# H1maria_v120_schematic.net
KiCad netlist of a schematic drawn in EAGLE
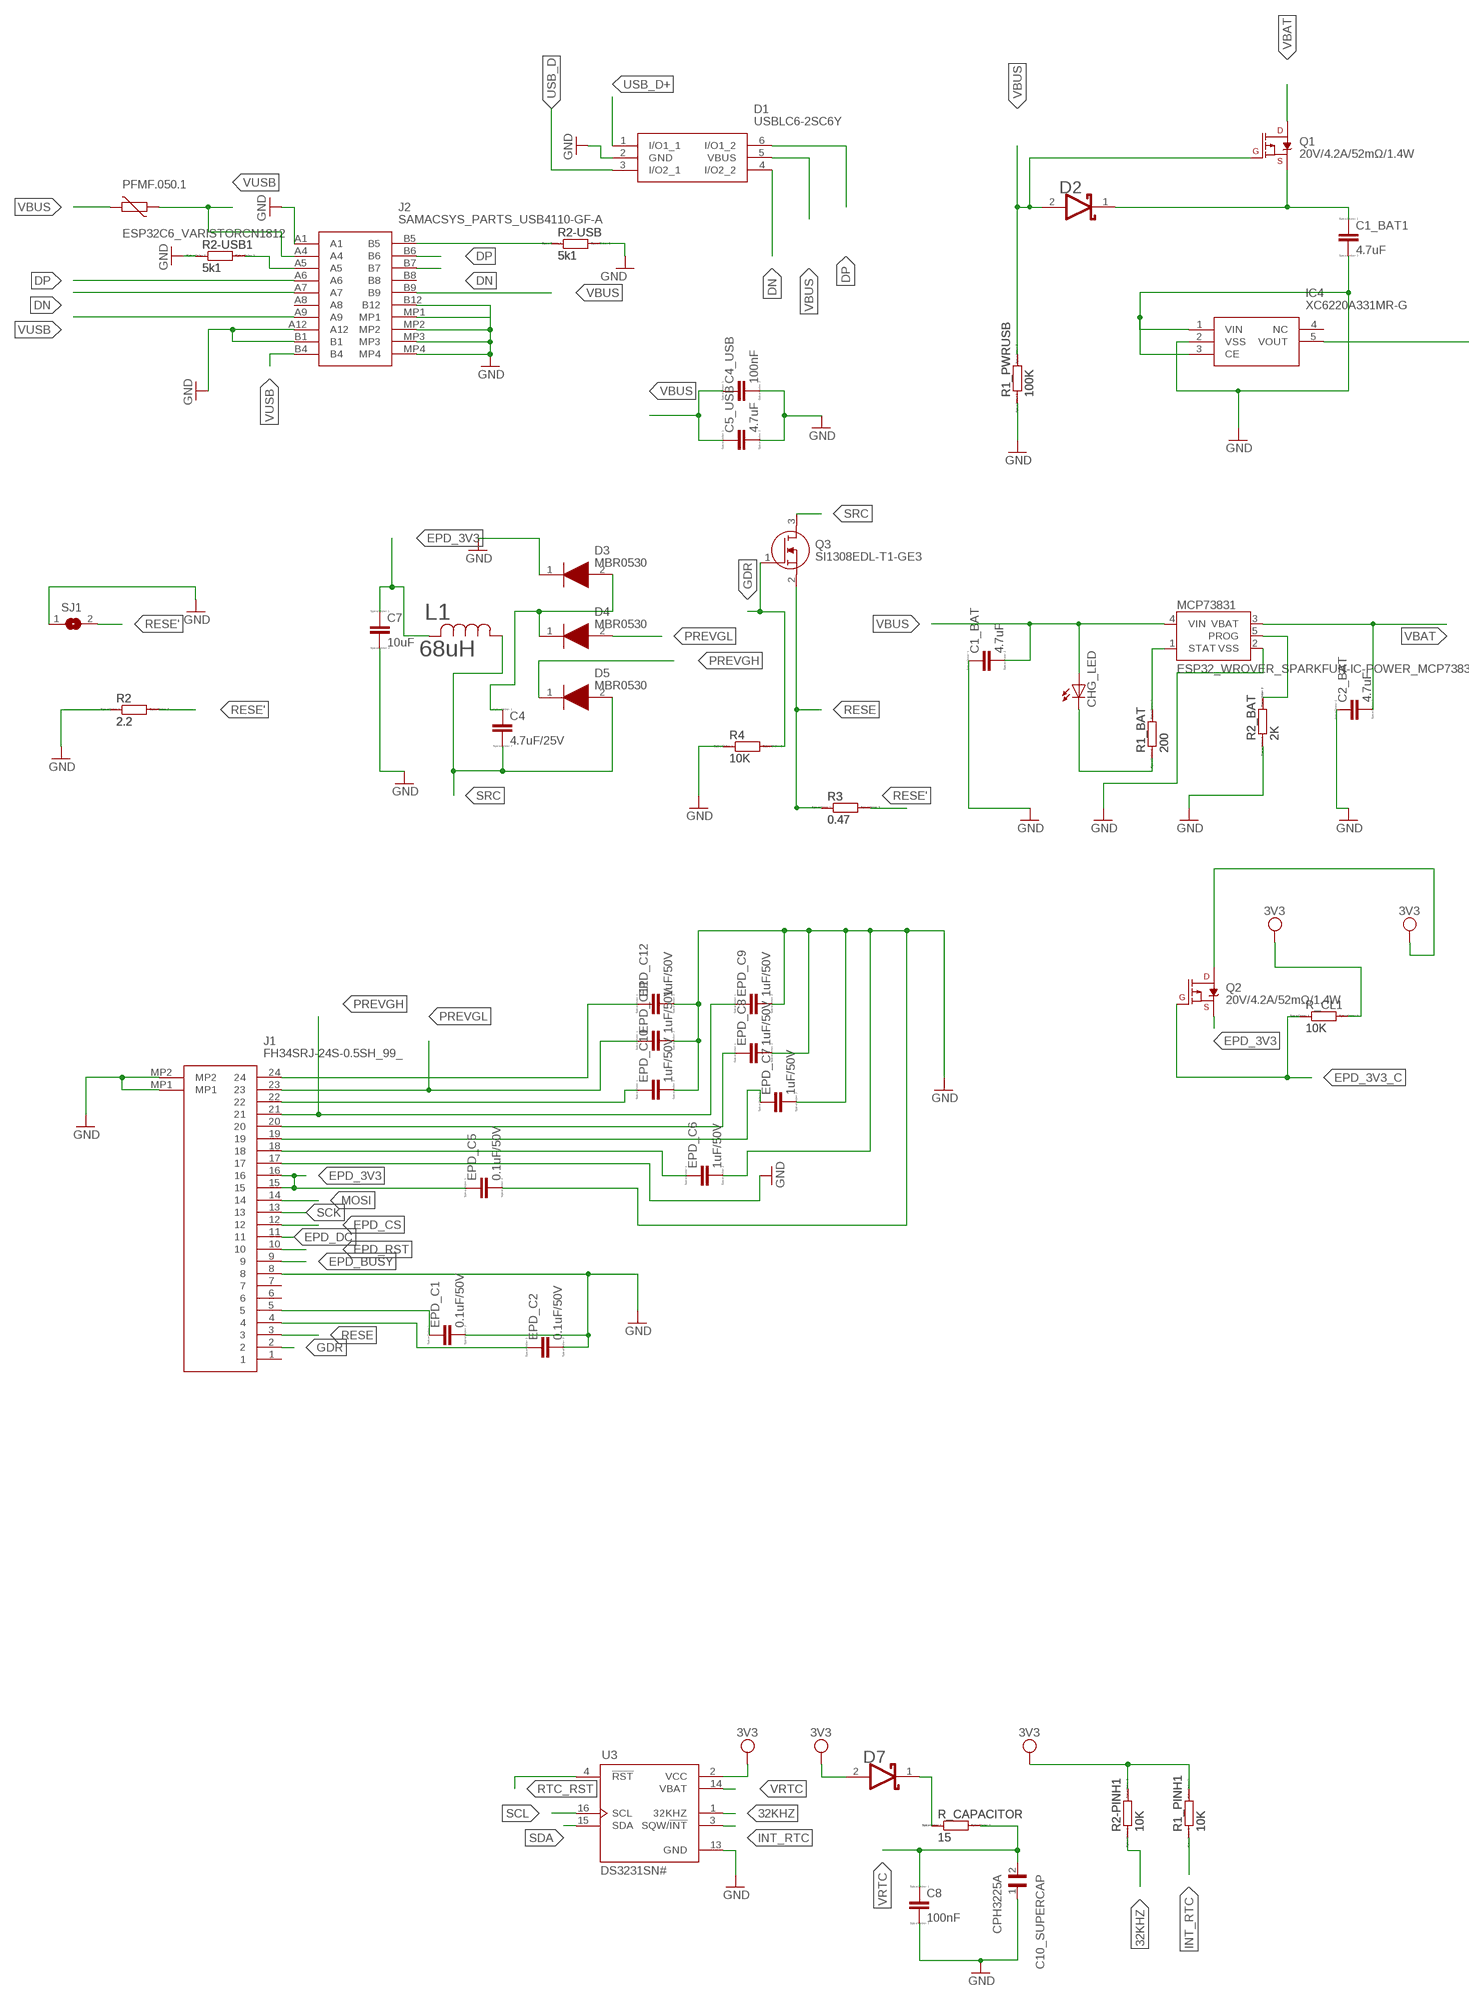
[diagram p0: schematic, sheet 1, part 1 of 2]
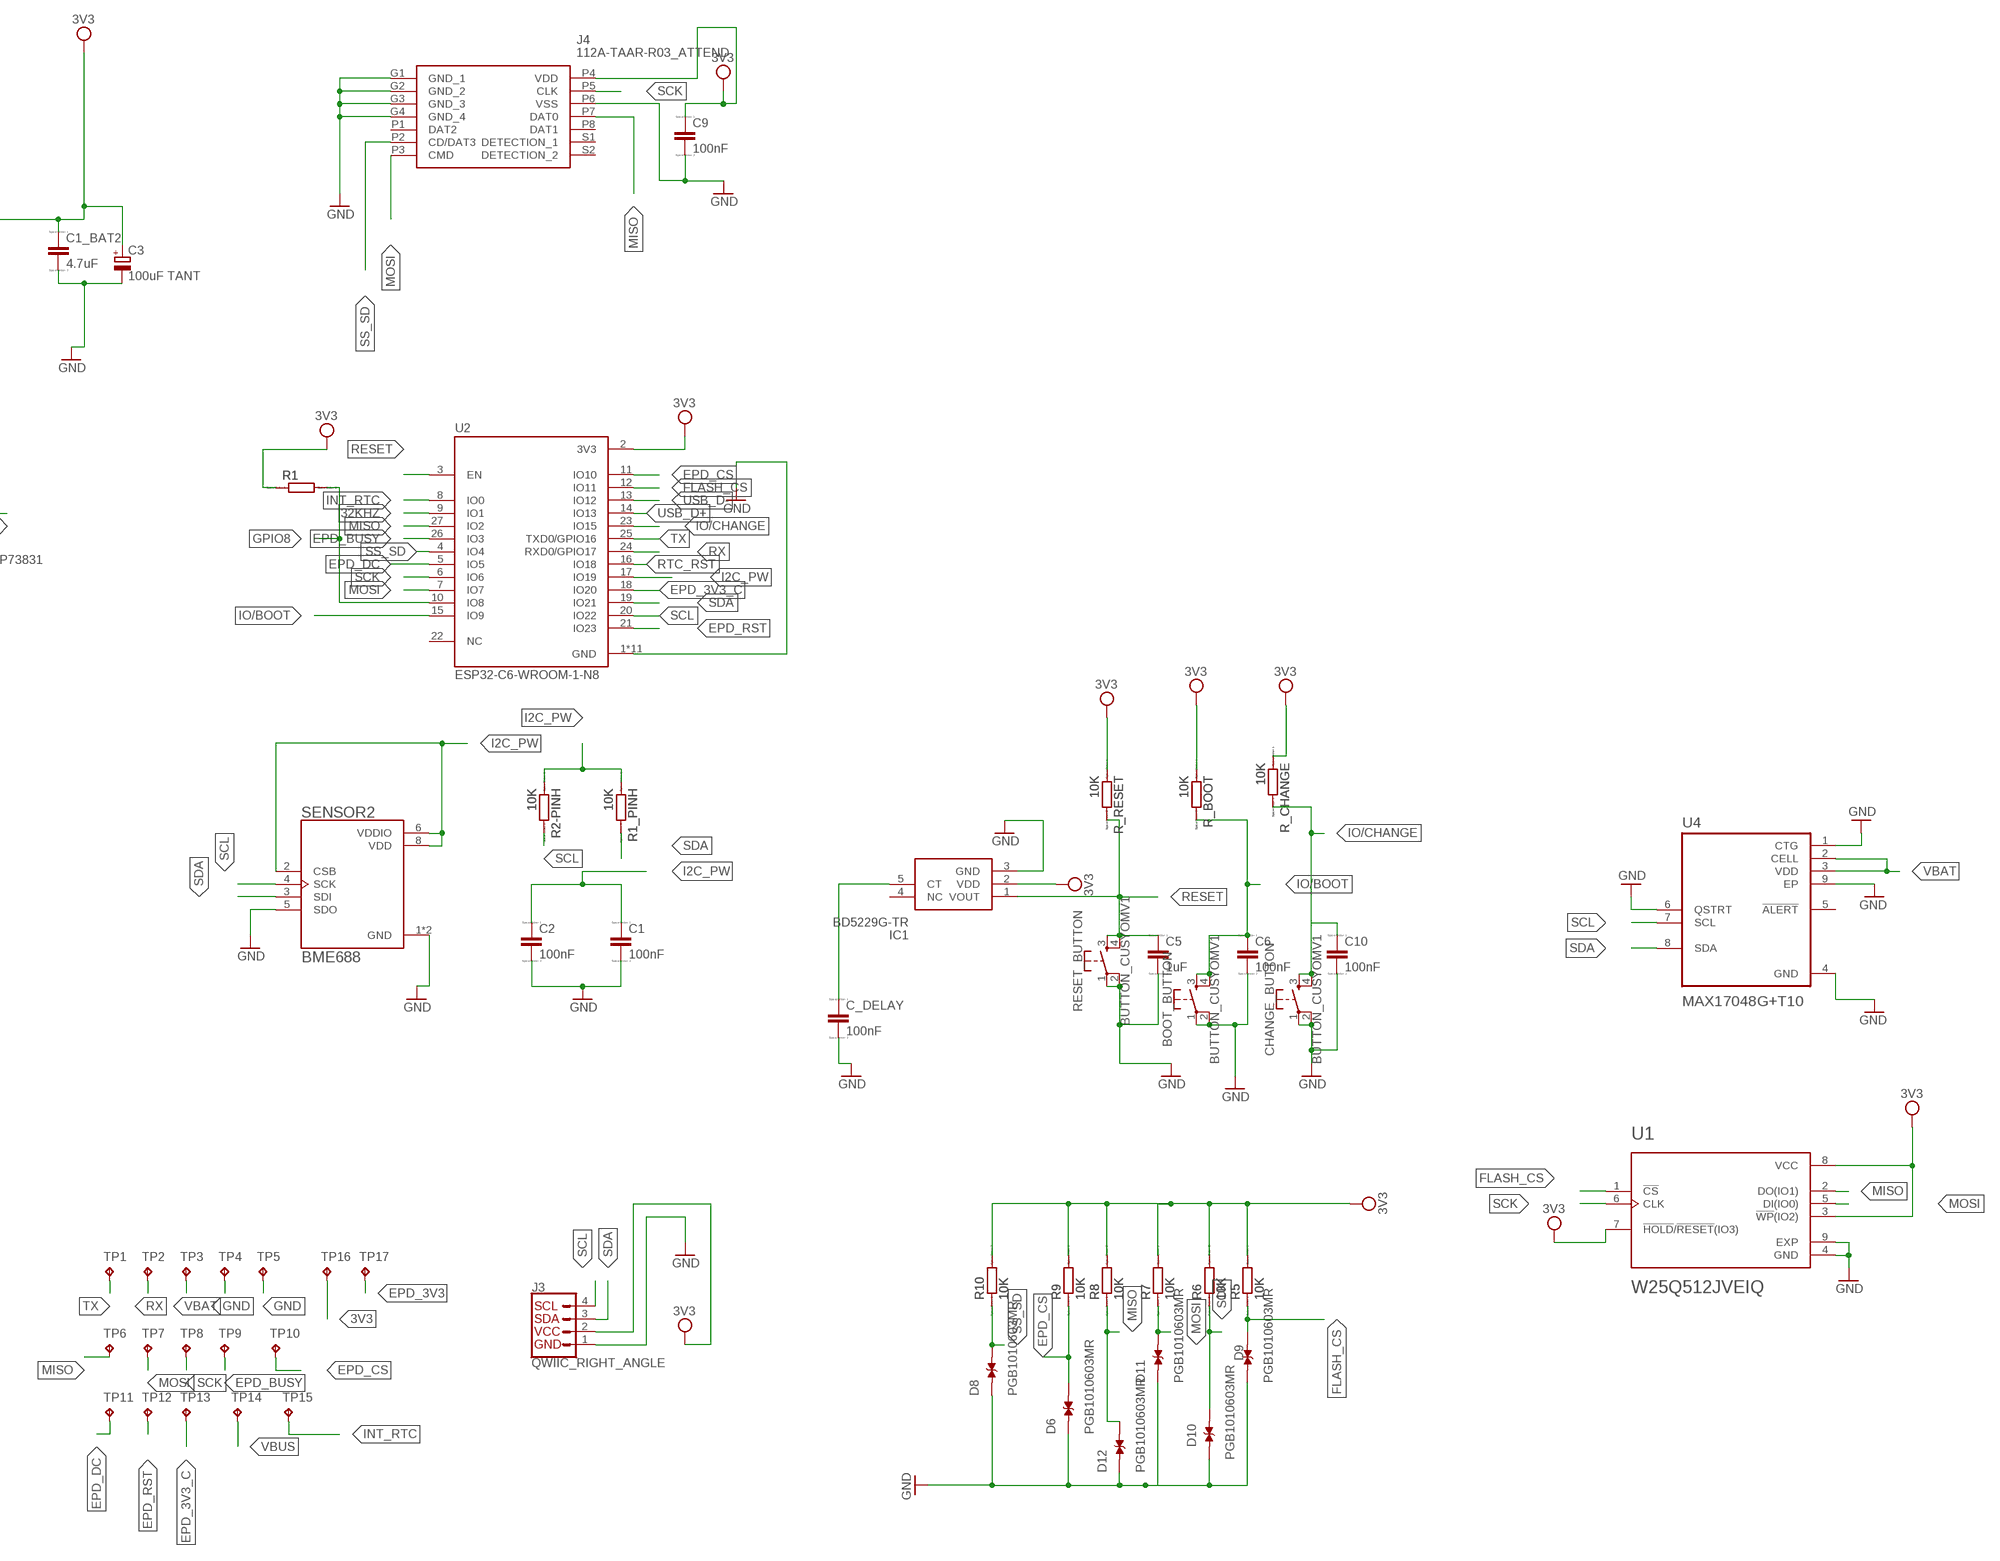
[diagram p1: schematic, sheet 1, part 2 of 2]

(export (version "E")
  (design (tool "Eeschema 10.0.6"))
  (components
    (comp (ref "BOOT_BUTTON")
      (value "BUTTON_CUSYOMV1")
      (footprint "eagle-import:MYBUTTON")
      (libsource (lib "eagle-import") (part "BUTTON_CUSYOMV1"))
    )
    (comp (ref "C1")
      (value "100nF")
      (footprint "eagle-import:ESP32_WROVER_EAGLE-LTSPICE_C0402")
      (libsource (lib "eagle-import") (part "ESP32_WROVER_EAGLE-LTSPICE_CC0402"))
    )
    (comp (ref "C1_BAT")
      (value "4.7uF")
      (footprint "eagle-import:EAGLE-LTSPICE_C0402")
      (libsource (lib "eagle-import") (part "EAGLE-LTSPICE_CC0402"))
    )
    (comp (ref "C1_BAT1")
      (value "4.7uF")
      (footprint "eagle-import:EAGLE-LTSPICE_C0402")
      (libsource (lib "eagle-import") (part "EAGLE-LTSPICE_CC0402"))
    )
    (comp (ref "C1_BAT2")
      (value "4.7uF")
      (footprint "eagle-import:EAGLE-LTSPICE_C0402")
      (libsource (lib "eagle-import") (part "EAGLE-LTSPICE_CC0402"))
    )
    (comp (ref "C2")
      (value "100nF")
      (footprint "eagle-import:ESP32_WROVER_EAGLE-LTSPICE_C0402")
      (libsource (lib "eagle-import") (part "ESP32_WROVER_EAGLE-LTSPICE_CC0402"))
    )
    (comp (ref "C2_BAT")
      (value "4.7uF")
      (footprint "eagle-import:EAGLE-LTSPICE_C0402")
      (libsource (lib "eagle-import") (part "EAGLE-LTSPICE_CC0402"))
    )
    (comp (ref "C3")
      (value "100uF TANT")
      (footprint "eagle-import:RCL_CT3528")
      (libsource (lib "eagle-import") (part "RCL_CPOL-EUCT3528"))
    )
    (comp (ref "C4")
      (value "4.7uF/25V")
      (footprint "eagle-import:ESP32_WROVER_EAGLE-LTSPICE_C0402")
      (libsource (lib "eagle-import") (part "ESP32_WROVER_EAGLE-LTSPICE_CC0402"))
    )
    (comp (ref "C4_USB")
      (value "100nF")
      (footprint "eagle-import:EAGLE-LTSPICE_C0402")
      (libsource (lib "eagle-import") (part "EAGLE-LTSPICE_CC0402"))
    )
    (comp (ref "C5")
      (value "1uF")
      (footprint "eagle-import:EAGLE-LTSPICE_C0402")
      (libsource (lib "eagle-import") (part "EAGLE-LTSPICE_CC0402"))
    )
    (comp (ref "C5_USB")
      (value "4.7uF")
      (footprint "eagle-import:EAGLE-LTSPICE_C0402")
      (libsource (lib "eagle-import") (part "EAGLE-LTSPICE_CC0402"))
    )
    (comp (ref "C6")
      (value "100nF")
      (footprint "eagle-import:EAGLE-LTSPICE_C0402")
      (libsource (lib "eagle-import") (part "EAGLE-LTSPICE_CC0402"))
    )
    (comp (ref "C7")
      (value "10uF")
      (footprint "eagle-import:ESP32_WROVER_EAGLE-LTSPICE_C0402")
      (libsource (lib "eagle-import") (part "ESP32_WROVER_EAGLE-LTSPICE_CC0402"))
    )
    (comp (ref "C8")
      (value "100nF")
      (footprint "eagle-import:EAGLE-LTSPICE_C0402")
      (libsource (lib "eagle-import") (part "EAGLE-LTSPICE_CC0402"))
    )
    (comp (ref "C9")
      (value "100nF")
      (footprint "eagle-import:ESP32_WROVER_EAGLE-LTSPICE_C0402")
      (libsource (lib "eagle-import") (part "ESP32_WROVER_EAGLE-LTSPICE_CC0402"))
    )
    (comp (ref "C10")
      (value "100nF")
      (footprint "eagle-import:EAGLE-LTSPICE_C0402")
      (libsource (lib "eagle-import") (part "EAGLE-LTSPICE_CC0402"))
    )
    (comp (ref "C10_SUPERCAP")
      (value "CPH3225A")
      (footprint "eagle-import:CAPCP3225X100N")
      (fields (field (name "MF") "Seiko Instruments"))
      (libsource (lib "eagle-import") (part "CPH3225A"))
    )
    (comp (ref "CHANGE_BUTTON")
      (value "BUTTON_CUSYOMV1")
      (footprint "eagle-import:MYBUTTON")
      (libsource (lib "eagle-import") (part "BUTTON_CUSYOMV1"))
    )
    (comp (ref "CHG_LED")
      (value "ADAFRUIT_LEDCHIP-LED0603")
      (footprint "eagle-import:ADAFRUIT_CHIP-LED0603")
      (libsource (lib "eagle-import") (part "ADAFRUIT_LEDCHIP-LED0603"))
    )
    (comp (ref "C_DELAY")
      (value "100nF")
      (footprint "eagle-import:EAGLE-LTSPICE_C0402")
      (libsource (lib "eagle-import") (part "EAGLE-LTSPICE_CC0402"))
    )
    (comp (ref "D1")
      (value "USBLC6-2SC6Y")
      (footprint "eagle-import:SOT95P280X145-6N")
      (fields (field (name "MF") "STMicroelectronics"))
      (libsource (lib "eagle-import") (part "USBLC6-2SC6Y"))
    )
    (comp (ref "D2")
      (value "SD0805S020S1R0")
      (footprint "eagle-import:ESP32_WROVER_AVX---SD0805S020S1R0_AVX_SD0805S020S1R0_0")
      (fields
        (field (name "DIGIKEY_PART_NUMBER") "478-7800-1-ND")
        (field (name "MF") "AVX")
        (field (name "MOUSER_PART_NUMBER") "581-SD0805S020S1R0")
      )
      (libsource (lib "eagle-import") (part "ESP32_WROVER_AVX---SD0805S020S1R0_AVX_SD0805S020S1R0_0_0AVX_SD0805S020S1R0_0_0"))
    )
    (comp (ref "D3")
      (value "MBR0530")
      (footprint "eagle-import:SOD3716X135N")
      (fields (field (name "MF") "ON Semiconductor"))
      (libsource (lib "eagle-import") (part "MBR0530"))
    )
    (comp (ref "D4")
      (value "MBR0530")
      (footprint "eagle-import:SOD3716X135N")
      (fields (field (name "MF") "ON Semiconductor"))
      (libsource (lib "eagle-import") (part "MBR0530"))
    )
    (comp (ref "D5")
      (value "MBR0530")
      (footprint "eagle-import:SOD3716X135N")
      (fields (field (name "MF") "ON Semiconductor"))
      (libsource (lib "eagle-import") (part "MBR0530"))
    )
    (comp (ref "D6")
      (value "PGB1010603MR")
      (footprint "eagle-import:DIOC1608X36N")
      (fields (field (name "MF") "Littelfuse Inc."))
      (libsource (lib "eagle-import") (part "PGB1010603MR"))
    )
    (comp (ref "D7")
      (value "ESP32_WROVER_AVX---SD0805S020S1R0_AVX_SD0805S020S1R0_0_0AVX_SD0805S020S1R0_0_0")
      (footprint "eagle-import:ESP32_WROVER_AVX---SD0805S020S1R0_AVX_SD0805S020S1R0_0")
      (fields
        (field (name "DIGIKEY_PART_NUMBER") "478-7800-1-ND")
        (field (name "MF") "AVX")
        (field (name "MOUSER_PART_NUMBER") "581-SD0805S020S1R0")
      )
      (libsource (lib "eagle-import") (part "ESP32_WROVER_AVX---SD0805S020S1R0_AVX_SD0805S020S1R0_0_0AVX_SD0805S020S1R0_0_0"))
    )
    (comp (ref "D8")
      (value "PGB1010603MR")
      (footprint "eagle-import:DIOC1608X36N")
      (fields (field (name "MF") "Littelfuse Inc."))
      (libsource (lib "eagle-import") (part "PGB1010603MR"))
    )
    (comp (ref "D9")
      (value "PGB1010603MR")
      (footprint "eagle-import:DIOC1608X36N")
      (fields (field (name "MF") "Littelfuse Inc."))
      (libsource (lib "eagle-import") (part "PGB1010603MR"))
    )
    (comp (ref "D10")
      (value "PGB1010603MR")
      (footprint "eagle-import:DIOC1608X36N")
      (fields (field (name "MF") "Littelfuse Inc."))
      (libsource (lib "eagle-import") (part "PGB1010603MR"))
    )
    (comp (ref "D11")
      (value "PGB1010603MR")
      (footprint "eagle-import:DIOC1608X36N")
      (fields (field (name "MF") "Littelfuse Inc."))
      (libsource (lib "eagle-import") (part "PGB1010603MR"))
    )
    (comp (ref "D12")
      (value "PGB1010603MR")
      (footprint "eagle-import:DIOC1608X36N")
      (fields (field (name "MF") "Littelfuse Inc."))
      (libsource (lib "eagle-import") (part "PGB1010603MR"))
    )
    (comp (ref "EPD_C1")
      (value "0.1uF/50V")
      (footprint "eagle-import:EAGLE-LTSPICE_C0402")
      (libsource (lib "eagle-import") (part "EAGLE-LTSPICE_CC0402"))
    )
    (comp (ref "EPD_C2")
      (value "0.1uF/50V")
      (footprint "eagle-import:EAGLE-LTSPICE_C0402")
      (libsource (lib "eagle-import") (part "EAGLE-LTSPICE_CC0402"))
    )
    (comp (ref "EPD_C5")
      (value "0.1uF/50V")
      (footprint "eagle-import:EAGLE-LTSPICE_C0402")
      (libsource (lib "eagle-import") (part "EAGLE-LTSPICE_CC0402"))
    )
    (comp (ref "EPD_C6")
      (value "1uF/50V")
      (footprint "eagle-import:EAGLE-LTSPICE_C0402")
      (libsource (lib "eagle-import") (part "EAGLE-LTSPICE_CC0402"))
    )
    (comp (ref "EPD_C7")
      (value "1uF/50V")
      (footprint "eagle-import:EAGLE-LTSPICE_C0402")
      (libsource (lib "eagle-import") (part "EAGLE-LTSPICE_CC0402"))
    )
    (comp (ref "EPD_C8")
      (value "1uF/50V")
      (footprint "eagle-import:EAGLE-LTSPICE_C0402")
      (libsource (lib "eagle-import") (part "EAGLE-LTSPICE_CC0402"))
    )
    (comp (ref "EPD_C9")
      (value "1uF/50V")
      (footprint "eagle-import:EAGLE-LTSPICE_C0402")
      (libsource (lib "eagle-import") (part "EAGLE-LTSPICE_CC0402"))
    )
    (comp (ref "EPD_C10")
      (value "1uF/50V")
      (footprint "eagle-import:EAGLE-LTSPICE_C0402")
      (libsource (lib "eagle-import") (part "EAGLE-LTSPICE_CC0402"))
    )
    (comp (ref "EPD_C11")
      (value "1uF/50V")
      (footprint "eagle-import:EAGLE-LTSPICE_C0402")
      (libsource (lib "eagle-import") (part "EAGLE-LTSPICE_CC0402"))
    )
    (comp (ref "EPD_C12")
      (value "1uF/50V")
      (footprint "eagle-import:EAGLE-LTSPICE_C0402")
      (libsource (lib "eagle-import") (part "EAGLE-LTSPICE_CC0402"))
    )
    (comp (ref "IC1")
      (value "BD5229G-TR")
      (footprint "eagle-import:SOT95P280X125-5N")
      (fields (field (name "MOUSER_PART_NUMBER") "755-BD5229G-TR"))
      (libsource (lib "eagle-import") (part "BD5229G-TR"))
    )
    (comp (ref "IC4")
      (value "XC6220A331MR-G")
      (footprint "eagle-import:SOT95P280X120-5N")
      (fields (field (name "MOUSER_PART_NUMBER") "865-XC6220A331MR-G"))
      (libsource (lib "eagle-import") (part "XC6220A331MR-G"))
    )
    (comp (ref "J1")
      (value "FH34SRJ-24S-0.5SH_99_")
      (footprint "eagle-import:FH34SRJ24S05SH99")
      (fields
        (field (name "MANUFACTURER_PART_NUMBER") "FH34SRJ-24S-0.5SH(99)")
        (field (name "MOUSER_PART_NUMBER") "798-FH34SRJ24S05SH99")
      )
      (libsource (lib "eagle-import") (part "FH34SRJ-24S-0.5SH_99_"))
    )
    (comp (ref "J2")
      (value "SAMACSYS_PARTS_USB4110-GF-A")
      (footprint "eagle-import:SAMACSYS_PARTS_USB4110GFA")
      (fields
        (field (name "MANUFACTURER_PART_NUMBER") "USB4110-GF-A")
        (field (name "MOUSER_PART_NUMBER") "640-USB4110-GF-A")
      )
      (libsource (lib "eagle-import") (part "SAMACSYS_PARTS_USB4110-GF-A"))
    )
    (comp (ref "J3")
      (value "QWIIC_RIGHT_ANGLE")
      (footprint "eagle-import:JST04_1MM_RA")
      (libsource (lib "eagle-import") (part "QWIIC_CONNECTORJS-1MM"))
    )
    (comp (ref "J4")
      (value "112A-TAAR-R03_ATTEND")
      (footprint "eagle-import:112ATAARR03ATTEND")
      (fields (field (name "MANUFACTURER_PART_NUMBER") "112A-TAAR-R03 ATTEND"))
      (libsource (lib "eagle-import") (part "112A-TAAR-R03_ATTEND"))
    )
    (comp (ref "L1")
      (value "68uH")
      (footprint "eagle-import:IND_4828-WE-TPC_WRE")
      (fields
        (field (name "MANUFACTURER_PART_NUMBER") "744043680")
        (field (name "COPYRIGHT") "Copyright (C) 2024 Ultra Librarian. All rights reserved.")
      )
      (libsource (lib "eagle-import") (part "744043680IND_4828-WE-TPC_WRE"))
    )
    (comp (ref "MCP73831")
      (value "ESP32_WROVER_SPARKFUN-IC-POWER_MCP73831")
      (footprint "eagle-import:ESP32_WROVER_SPARKFUN-IC-POWER_SOT23-5")
      (libsource (lib "eagle-import") (part "ESP32_WROVER_SPARKFUN-IC-POWER_MCP73831"))
    )
    (comp (ref "PFMF.050.1")
      (value "ESP32C6_VARISTORCN1812")
      (footprint "eagle-import:ESP32C6_VARISTOR_CT_CN1812")
      (libsource (lib "eagle-import") (part "ESP32C6_VARISTORCN1812"))
    )
    (comp (ref "Q1")
      (value "20V/4.2A/52mΩ/1.4W")
      (footprint "eagle-import:ESP32_WROVER_SPARKFUN-DISCRETESEMI_SOT23-3")
      (libsource (lib "eagle-import") (part "ESP32_WROVER_SPARKFUN-DISCRETESEMI_MOSFET_PCH-DMG2305UX-7"))
    )
    (comp (ref "Q2")
      (value "20V/4.2A/52mΩ/1.4W")
      (footprint "eagle-import:ESP32_WROVER_SPARKFUN-DISCRETESEMI_SOT23-3")
      (libsource (lib "eagle-import") (part "ESP32_WROVER_SPARKFUN-DISCRETESEMI_MOSFET_PCH-DMG2305UX-7"))
    )
    (comp (ref "Q3")
      (value "SI1308EDL-T1-GE3")
      (footprint "eagle-import:SOT65P210X110-3N")
      (fields (field (name "MF") "Vishay Siliconix"))
      (libsource (lib "eagle-import") (part "SI1308EDL-T1-GE3"))
    )
    (comp (ref "R1")
      (value "ESP32_WROVER_EAGLE-LTSPICE_RR0402")
      (footprint "eagle-import:ESP32_WROVER_EAGLE-LTSPICE_R0402")
      (libsource (lib "eagle-import") (part "ESP32_WROVER_EAGLE-LTSPICE_RR0402"))
    )
    (comp (ref "R1_BAT")
      (value "200")
      (footprint "eagle-import:ESP32_WROVER_EAGLE-LTSPICE_R0402")
      (libsource (lib "eagle-import") (part "ESP32_WROVER_EAGLE-LTSPICE_RR0402"))
    )
    (comp (ref "R1_PINH")
      (value "10K")
      (footprint "eagle-import:ESP32_WROVER_EAGLE-LTSPICE_R0402")
      (libsource (lib "eagle-import") (part "ESP32_WROVER_EAGLE-LTSPICE_RR0402"))
    )
    (comp (ref "R1_PINH1")
      (value "10K")
      (footprint "eagle-import:ESP32_WROVER_EAGLE-LTSPICE_R0402")
      (libsource (lib "eagle-import") (part "ESP32_WROVER_EAGLE-LTSPICE_RR0402"))
    )
    (comp (ref "R1_PWRUSB")
      (value "100K")
      (footprint "eagle-import:ESP32_WROVER_EAGLE-LTSPICE_R0402")
      (libsource (lib "eagle-import") (part "ESP32_WROVER_EAGLE-LTSPICE_RR0402"))
    )
    (comp (ref "R2")
      (value "2.2")
      (footprint "eagle-import:ESP32_WROVER_EAGLE-LTSPICE_R0402")
      (libsource (lib "eagle-import") (part "ESP32_WROVER_EAGLE-LTSPICE_RR0402"))
    )
    (comp (ref "R2-PINH")
      (value "10K")
      (footprint "eagle-import:ESP32_WROVER_EAGLE-LTSPICE_R0402")
      (libsource (lib "eagle-import") (part "ESP32_WROVER_EAGLE-LTSPICE_RR0402"))
    )
    (comp (ref "R2-PINH1")
      (value "10K")
      (footprint "eagle-import:ESP32_WROVER_EAGLE-LTSPICE_R0402")
      (libsource (lib "eagle-import") (part "ESP32_WROVER_EAGLE-LTSPICE_RR0402"))
    )
    (comp (ref "R2-USB")
      (value "5k1")
      (footprint "eagle-import:ESP32_WROVER_EAGLE-LTSPICE_R0402")
      (libsource (lib "eagle-import") (part "ESP32_WROVER_EAGLE-LTSPICE_RR0402"))
    )
    (comp (ref "R2-USB1")
      (value "5k1")
      (footprint "eagle-import:ESP32_WROVER_EAGLE-LTSPICE_R0402")
      (libsource (lib "eagle-import") (part "ESP32_WROVER_EAGLE-LTSPICE_RR0402"))
    )
    (comp (ref "R2_BAT")
      (value "2K")
      (footprint "eagle-import:ESP32_WROVER_EAGLE-LTSPICE_R0402")
      (libsource (lib "eagle-import") (part "ESP32_WROVER_EAGLE-LTSPICE_RR0402"))
    )
    (comp (ref "R3")
      (value "0.47")
      (footprint "eagle-import:ESP32_WROVER_EAGLE-LTSPICE_R0402")
      (libsource (lib "eagle-import") (part "ESP32_WROVER_EAGLE-LTSPICE_RR0402"))
    )
    (comp (ref "R4")
      (value "10K")
      (footprint "eagle-import:ESP32_WROVER_EAGLE-LTSPICE_R0402")
      (libsource (lib "eagle-import") (part "ESP32_WROVER_EAGLE-LTSPICE_RR0402"))
    )
    (comp (ref "R5")
      (value "10K")
      (footprint "eagle-import:ESP32_WROVER_EAGLE-LTSPICE_R0402")
      (libsource (lib "eagle-import") (part "ESP32_WROVER_EAGLE-LTSPICE_RR0402"))
    )
    (comp (ref "R6")
      (value "10K")
      (footprint "eagle-import:ESP32_WROVER_EAGLE-LTSPICE_R0402")
      (libsource (lib "eagle-import") (part "ESP32_WROVER_EAGLE-LTSPICE_RR0402"))
    )
    (comp (ref "R7")
      (value "10K")
      (footprint "eagle-import:ESP32_WROVER_EAGLE-LTSPICE_R0402")
      (libsource (lib "eagle-import") (part "ESP32_WROVER_EAGLE-LTSPICE_RR0402"))
    )
    (comp (ref "R8")
      (value "10K")
      (footprint "eagle-import:ESP32_WROVER_EAGLE-LTSPICE_R0402")
      (libsource (lib "eagle-import") (part "ESP32_WROVER_EAGLE-LTSPICE_RR0402"))
    )
    (comp (ref "R9")
      (value "10K")
      (footprint "eagle-import:ESP32_WROVER_EAGLE-LTSPICE_R0402")
      (libsource (lib "eagle-import") (part "ESP32_WROVER_EAGLE-LTSPICE_RR0402"))
    )
    (comp (ref "R10")
      (value "10K")
      (footprint "eagle-import:ESP32_WROVER_EAGLE-LTSPICE_R0402")
      (libsource (lib "eagle-import") (part "ESP32_WROVER_EAGLE-LTSPICE_RR0402"))
    )
    (comp (ref "RESET_BUTTON")
      (value "BUTTON_CUSYOMV1")
      (footprint "eagle-import:MYBUTTON")
      (libsource (lib "eagle-import") (part "BUTTON_CUSYOMV1"))
    )
    (comp (ref "R_BOOT")
      (value "10K")
      (footprint "eagle-import:ESP32_WROVER_EAGLE-LTSPICE_R0402")
      (libsource (lib "eagle-import") (part "ESP32_WROVER_EAGLE-LTSPICE_RR0402"))
    )
    (comp (ref "R_CAPACITOR")
      (value "15")
      (footprint "eagle-import:ESP32_WROVER_EAGLE-LTSPICE_R0402")
      (libsource (lib "eagle-import") (part "ESP32_WROVER_EAGLE-LTSPICE_RR0402"))
    )
    (comp (ref "R_CHANGE")
      (value "10K")
      (footprint "eagle-import:ESP32_WROVER_EAGLE-LTSPICE_R0402")
      (libsource (lib "eagle-import") (part "ESP32_WROVER_EAGLE-LTSPICE_RR0402"))
    )
    (comp (ref "R_CL1")
      (value "10K")
      (footprint "eagle-import:ESP32_WROVER_EAGLE-LTSPICE_R0402")
      (libsource (lib "eagle-import") (part "ESP32_WROVER_EAGLE-LTSPICE_RR0402"))
    )
    (comp (ref "R_RESET")
      (value "10K")
      (footprint "eagle-import:ESP32_WROVER_EAGLE-LTSPICE_R0402")
      (libsource (lib "eagle-import") (part "ESP32_WROVER_EAGLE-LTSPICE_RR0402"))
    )
    (comp (ref "SENSOR2")
      (value "BME688")
      (footprint "eagle-import:ESP32_WROVER_BME680_PSON80P300X300X100-8N")
      (fields (field (name "MF") "Bosch Sensortec") (field (name "MP") "BME680"))
      (libsource (lib "eagle-import") (part "ESP32_WROVER_BME680_BME680"))
    )
    (comp (ref "SJ1") (value "SJ") (footprint "eagle-import:SJ") (libsource (lib "eagle-import") (part "SJ")))
    (comp (ref "TP1")
      (value "TPTP20R")
      (footprint "eagle-import:TP20R")
      (libsource (lib "eagle-import") (part "TPTP20R"))
    )
    (comp (ref "TP2")
      (value "TPTP20R")
      (footprint "eagle-import:TP20R")
      (libsource (lib "eagle-import") (part "TPTP20R"))
    )
    (comp (ref "TP3")
      (value "TPTP20R")
      (footprint "eagle-import:TP20R")
      (libsource (lib "eagle-import") (part "TPTP20R"))
    )
    (comp (ref "TP4")
      (value "TPTP20R")
      (footprint "eagle-import:TP20R")
      (libsource (lib "eagle-import") (part "TPTP20R"))
    )
    (comp (ref "TP5")
      (value "TPTP20R")
      (footprint "eagle-import:TP20R")
      (libsource (lib "eagle-import") (part "TPTP20R"))
    )
    (comp (ref "TP6")
      (value "TPTP20R")
      (footprint "eagle-import:TP20R")
      (libsource (lib "eagle-import") (part "TPTP20R"))
    )
    (comp (ref "TP7")
      (value "TPTP20R")
      (footprint "eagle-import:TP20R")
      (libsource (lib "eagle-import") (part "TPTP20R"))
    )
    (comp (ref "TP8")
      (value "TPTP20R")
      (footprint "eagle-import:TP20R")
      (libsource (lib "eagle-import") (part "TPTP20R"))
    )
    (comp (ref "TP9")
      (value "TPTP20R")
      (footprint "eagle-import:TP20R")
      (libsource (lib "eagle-import") (part "TPTP20R"))
    )
    (comp (ref "TP10")
      (value "TPTP20R")
      (footprint "eagle-import:TP20R")
      (libsource (lib "eagle-import") (part "TPTP20R"))
    )
    (comp (ref "TP11")
      (value "TPTP20R")
      (footprint "eagle-import:TP20R")
      (libsource (lib "eagle-import") (part "TPTP20R"))
    )
    (comp (ref "TP12")
      (value "TPTP20R")
      (footprint "eagle-import:TP20R")
      (libsource (lib "eagle-import") (part "TPTP20R"))
    )
    (comp (ref "TP13")
      (value "TPTP20R")
      (footprint "eagle-import:TP20R")
      (libsource (lib "eagle-import") (part "TPTP20R"))
    )
    (comp (ref "TP14")
      (value "TPTP20R")
      (footprint "eagle-import:TP20R")
      (libsource (lib "eagle-import") (part "TPTP20R"))
    )
    (comp (ref "TP15")
      (value "TPTP20R")
      (footprint "eagle-import:TP20R")
      (libsource (lib "eagle-import") (part "TPTP20R"))
    )
    (comp (ref "TP16")
      (value "TPTP20R")
      (footprint "eagle-import:TP20R")
      (libsource (lib "eagle-import") (part "TPTP20R"))
    )
    (comp (ref "TP17")
      (value "TPTP20R")
      (footprint "eagle-import:TP20R")
      (libsource (lib "eagle-import") (part "TPTP20R"))
    )
    (comp (ref "U1")
      (value "W25Q512JVEIQ")
      (footprint "eagle-import:SON127P600X800X80-9N")
      (fields (field (name "MF") "Winbond Electronics"))
      (libsource (lib "eagle-import") (part "W25Q512JVEIQ"))
    )
    (comp (ref "U2")
      (value "ESP32-C6-WROOM-1-N8")
      (footprint "eagle-import:XCVR_ESP32-C6-WROOM-1-N8")
      (fields (field (name "MF") "Espressif Systems"))
      (libsource (lib "eagle-import") (part "ESP32-C6-WROOM-1-N8"))
    )
    (comp (ref "U3")
      (value "DS3231SN#")
      (footprint "eagle-import:SOIC127P1032X265-16N")
      (fields (field (name "MF") "Analog Devices"))
      (libsource (lib "eagle-import") (part "DS3231SN#"))
    )
    (comp (ref "U4")
      (value "MAX17048G+T10")
      (footprint "eagle-import:SON50P200X200X80-9N")
      (fields (field (name "MF") "Analog Devices"))
      (libsource (lib "eagle-import") (part "MAX17048G+T10"))
    )
  )
  (nets
    (net (code "1") (name "3V3") (class "Default")
      (node (ref "C1_BAT2") (pin "1") (pinfunction "1_1") (pintype "passive"))
      (node (ref "C3") (pin "+") (pinfunction "+_+") (pintype "passive"))
      (node (ref "C9") (pin "1") (pinfunction "1_1") (pintype "passive"))
      (node (ref "D7") (pin "2") (pinfunction "ANODE_2") (pintype "bidirectional"))
      (node (ref "IC1") (pin "2") (pinfunction "VDD_2") (pintype "bidirectional"))
      (node (ref "IC4") (pin "5") (pinfunction "VOUT_5") (pintype "bidirectional"))
      (node (ref "J3") (pin "2") (pinfunction "2_2") (pintype "power_in"))
      (node (ref "J4") (pin "P4") (pinfunction "VDD_P4") (pintype "bidirectional"))
      (node (ref "Q2") (pin "3") (pinfunction "D_3") (pintype "bidirectional"))
      (node (ref "R1") (pin "1") (pinfunction "1_1") (pintype "passive"))
      (node (ref "R10") (pin "2") (pinfunction "2_2") (pintype "passive"))
      (node (ref "R1_PINH1") (pin "2") (pinfunction "2_2") (pintype "passive"))
      (node (ref "R2-PINH1") (pin "2") (pinfunction "2_2") (pintype "passive"))
      (node (ref "R5") (pin "2") (pinfunction "2_2") (pintype "passive"))
      (node (ref "R6") (pin "2") (pinfunction "2_2") (pintype "passive"))
      (node (ref "R7") (pin "2") (pinfunction "2_2") (pintype "passive"))
      (node (ref "R8") (pin "2") (pinfunction "2_2") (pintype "passive"))
      (node (ref "R9") (pin "2") (pinfunction "2_2") (pintype "passive"))
      (node (ref "R_BOOT") (pin "1") (pinfunction "1_1") (pintype "passive"))
      (node (ref "R_CHANGE") (pin "1") (pinfunction "1_1") (pintype "passive"))
      (node (ref "R_CL1") (pin "2") (pinfunction "2_2") (pintype "passive"))
      (node (ref "R_RESET") (pin "1") (pinfunction "1_1") (pintype "passive"))
      (node (ref "TP16") (pin "TP") (pinfunction "TP_TP") (pintype "input"))
      (node (ref "U1") (pin "3") (pinfunction "~{WP}(IO2)_3") (pintype "bidirectional"))
      (node (ref "U1") (pin "7") (pinfunction "~{HOLD}/~{RESET}(IO3)_7") (pintype "bidirectional"))
      (node (ref "U1") (pin "8") (pinfunction "VCC_8") (pintype "power_in"))
      (node (ref "U2") (pin "2") (pinfunction "3V3_2") (pintype "power_in"))
      (node (ref "U3") (pin "2") (pinfunction "VCC_2") (pintype "power_in"))
    )
    (net (code "2") (name "32KHZ") (class "Default")
      (node (ref "R2-PINH1") (pin "1") (pinfunction "1_1") (pintype "passive"))
      (node (ref "U2") (pin "9") (pinfunction "IO1_9") (pintype "bidirectional"))
      (node (ref "U3") (pin "1") (pinfunction "32KHZ_1") (pintype "output"))
    )
    (net (code "3") (name "DN") (class "Default")
      (node (ref "D1") (pin "4") (pinfunction "I/O2_2_4") (pintype "bidirectional"))
      (node (ref "J2") (pin "A7") (pinfunction "A7_A7") (pintype "bidirectional"))
      (node (ref "J2") (pin "B7") (pinfunction "B7_B7") (pintype "bidirectional"))
    )
    (net (code "4") (name "DP") (class "Default")
      (node (ref "D1") (pin "6") (pinfunction "I/O1_2_6") (pintype "bidirectional"))
      (node (ref "J2") (pin "A6") (pinfunction "A6_A6") (pintype "bidirectional"))
      (node (ref "J2") (pin "B6") (pinfunction "B6_B6") (pintype "bidirectional"))
    )
    (net (code "5") (name "EPD_3V3") (class "Default")
      (node (ref "C7") (pin "1") (pinfunction "1_1") (pintype "passive"))
      (node (ref "EPD_C5") (pin "1") (pinfunction "1_1") (pintype "passive"))
      (node (ref "J1") (pin "15") (pinfunction "15_15") (pintype "bidirectional"))
      (node (ref "J1") (pin "16") (pinfunction "16_16") (pintype "bidirectional"))
      (node (ref "L1") (pin "2") (pinfunction "2_2") (pintype "passive"))
      (node (ref "Q2") (pin "2") (pinfunction "S_2") (pintype "bidirectional"))
      (node (ref "TP17") (pin "TP") (pinfunction "TP_TP") (pintype "input"))
    )
    (net (code "6") (name "EPD_3V3_C") (class "Default")
      (node (ref "Q2") (pin "1") (pinfunction "G_1") (pintype "bidirectional"))
      (node (ref "R_CL1") (pin "1") (pinfunction "1_1") (pintype "passive"))
      (node (ref "TP13") (pin "TP") (pinfunction "TP_TP") (pintype "input"))
      (node (ref "U2") (pin "18") (pinfunction "IO20_18") (pintype "bidirectional"))
    )
    (net (code "7") (name "EPD_BUSY") (class "Default")
      (node (ref "J1") (pin "9") (pinfunction "9_9") (pintype "bidirectional"))
      (node (ref "TP9") (pin "TP") (pinfunction "TP_TP") (pintype "input"))
      (node (ref "U2") (pin "26") (pinfunction "IO3_26") (pintype "bidirectional"))
    )
    (net (code "8") (name "EPD_CS") (class "Default")
      (node (ref "D6") (pin "2") (pinfunction "2_2") (pintype "passive"))
      (node (ref "J1") (pin "12") (pinfunction "12_12") (pintype "bidirectional"))
      (node (ref "R9") (pin "1") (pinfunction "1_1") (pintype "passive"))
      (node (ref "TP10") (pin "TP") (pinfunction "TP_TP") (pintype "input"))
      (node (ref "U2") (pin "11") (pinfunction "IO10_11") (pintype "bidirectional"))
    )
    (net (code "9") (name "EPD_DC") (class "Default")
      (node (ref "J1") (pin "11") (pinfunction "11_11") (pintype "bidirectional"))
      (node (ref "TP11") (pin "TP") (pinfunction "TP_TP") (pintype "input"))
      (node (ref "U2") (pin "5") (pinfunction "IO5_5") (pintype "bidirectional"))
    )
    (net (code "10") (name "EPD_RST") (class "Default")
      (node (ref "J1") (pin "10") (pinfunction "10_10") (pintype "bidirectional"))
      (node (ref "TP12") (pin "TP") (pinfunction "TP_TP") (pintype "input"))
      (node (ref "U2") (pin "21") (pinfunction "IO23_21") (pintype "bidirectional"))
    )
    (net (code "11") (name "FLASH_CS") (class "Default")
      (node (ref "D9") (pin "2") (pinfunction "2_2") (pintype "passive"))
      (node (ref "R5") (pin "1") (pinfunction "1_1") (pintype "passive"))
      (node (ref "U1") (pin "1") (pinfunction "~{CS}_1") (pintype "input"))
      (node (ref "U2") (pin "12") (pinfunction "IO11_12") (pintype "bidirectional"))
    )
    (net (code "12") (name "GDR") (class "Default")
      (node (ref "J1") (pin "2") (pinfunction "2_2") (pintype "bidirectional"))
      (node (ref "Q3") (pin "1") (pinfunction "G_1") (pintype "bidirectional"))
      (node (ref "R4") (pin "2") (pinfunction "2_2") (pintype "passive"))
    )
    (net (code "13") (name "GND") (class "Default")
      (node (ref "BOOT_BUTTON") (pin "1") (pinfunction "1_1") (pintype "passive"))
      (node (ref "BOOT_BUTTON") (pin "2") (pinfunction "2_2") (pintype "passive"))
      (node (ref "C1") (pin "2") (pinfunction "2_2") (pintype "passive"))
      (node (ref "C10") (pin "2") (pinfunction "2_2") (pintype "passive"))
      (node (ref "C10_SUPERCAP") (pin "1") (pinfunction "1_1") (pintype "passive"))
      (node (ref "C1_BAT") (pin "1") (pinfunction "1_1") (pintype "passive"))
      (node (ref "C1_BAT1") (pin "2") (pinfunction "2_2") (pintype "passive"))
      (node (ref "C1_BAT2") (pin "2") (pinfunction "2_2") (pintype "passive"))
      (node (ref "C2") (pin "2") (pinfunction "2_2") (pintype "passive"))
      (node (ref "C2_BAT") (pin "1") (pinfunction "1_1") (pintype "passive"))
      (node (ref "C3") (pin "-") (pinfunction "-_-") (pintype "passive"))
      (node (ref "C4_USB") (pin "2") (pinfunction "2_2") (pintype "passive"))
      (node (ref "C5") (pin "2") (pinfunction "2_2") (pintype "passive"))
      (node (ref "C5_USB") (pin "2") (pinfunction "2_2") (pintype "passive"))
      (node (ref "C6") (pin "2") (pinfunction "2_2") (pintype "passive"))
      (node (ref "C7") (pin "2") (pinfunction "2_2") (pintype "passive"))
      (node (ref "C8") (pin "2") (pinfunction "2_2") (pintype "passive"))
      (node (ref "C9") (pin "2") (pinfunction "2_2") (pintype "passive"))
      (node (ref "CHANGE_BUTTON") (pin "1") (pinfunction "1_1") (pintype "passive"))
      (node (ref "CHANGE_BUTTON") (pin "2") (pinfunction "2_2") (pintype "passive"))
      (node (ref "C_DELAY") (pin "2") (pinfunction "2_2") (pintype "passive"))
      (node (ref "D1") (pin "2") (pinfunction "GND_2") (pintype "bidirectional"))
      (node (ref "D10") (pin "1") (pinfunction "1_1") (pintype "passive"))
      (node (ref "D11") (pin "1") (pinfunction "1_1") (pintype "passive"))
      (node (ref "D12") (pin "1") (pinfunction "1_1") (pintype "passive"))
      (node (ref "D3") (pin "1") (pinfunction "K_1") (pintype "bidirectional"))
      (node (ref "D6") (pin "1") (pinfunction "1_1") (pintype "passive"))
      (node (ref "D8") (pin "1") (pinfunction "1_1") (pintype "passive"))
      (node (ref "D9") (pin "1") (pinfunction "1_1") (pintype "passive"))
      (node (ref "EPD_C1") (pin "2") (pinfunction "2_2") (pintype "passive"))
      (node (ref "EPD_C10") (pin "2") (pinfunction "2_2") (pintype "passive"))
      (node (ref "EPD_C11") (pin "2") (pinfunction "2_2") (pintype "passive"))
      (node (ref "EPD_C12") (pin "2") (pinfunction "2_2") (pintype "passive"))
      (node (ref "EPD_C2") (pin "2") (pinfunction "2_2") (pintype "passive"))
      (node (ref "EPD_C5") (pin "2") (pinfunction "2_2") (pintype "passive"))
      (node (ref "EPD_C6") (pin "2") (pinfunction "2_2") (pintype "passive"))
      (node (ref "EPD_C7") (pin "2") (pinfunction "2_2") (pintype "passive"))
      (node (ref "EPD_C8") (pin "2") (pinfunction "2_2") (pintype "passive"))
      (node (ref "EPD_C9") (pin "2") (pinfunction "2_2") (pintype "passive"))
      (node (ref "IC1") (pin "3") (pinfunction "GND_3") (pintype "bidirectional"))
      (node (ref "IC4") (pin "1") (pinfunction "VIN_1") (pintype "bidirectional"))
      (node (ref "IC4") (pin "2") (pinfunction "VSS_2") (pintype "bidirectional"))
      (node (ref "IC4") (pin "3") (pinfunction "CE_3") (pintype "bidirectional"))
      (node (ref "J1") (pin "17") (pinfunction "17_17") (pintype "bidirectional"))
      (node (ref "J1") (pin "8") (pinfunction "8_8") (pintype "bidirectional"))
      (node (ref "J1") (pin "MP1") (pinfunction "MP1_MP1") (pintype "bidirectional"))
      (node (ref "J1") (pin "MP2") (pinfunction "MP2_MP2") (pintype "bidirectional"))
      (node (ref "J2") (pin "A1") (pinfunction "A1_A1") (pintype "bidirectional"))
      (node (ref "J2") (pin "A12") (pinfunction "A12_A12") (pintype "bidirectional"))
      (node (ref "J2") (pin "B1") (pinfunction "B1_B1") (pintype "bidirectional"))
      (node (ref "J2") (pin "B12") (pinfunction "B12_B12") (pintype "bidirectional"))
      (node (ref "J2") (pin "MP1") (pinfunction "MP1_MP1") (pintype "bidirectional"))
      (node (ref "J2") (pin "MP2") (pinfunction "MP2_MP2") (pintype "bidirectional"))
      (node (ref "J2") (pin "MP3") (pinfunction "MP3_MP3") (pintype "bidirectional"))
      (node (ref "J2") (pin "MP4") (pinfunction "MP4_MP4") (pintype "bidirectional"))
      (node (ref "J3") (pin "1") (pinfunction "1_1") (pintype "power_in"))
      (node (ref "J4") (pin "G1") (pinfunction "GND_1_G1") (pintype "bidirectional"))
      (node (ref "J4") (pin "G2") (pinfunction "GND_2_G2") (pintype "bidirectional"))
      (node (ref "J4") (pin "G3") (pinfunction "GND_3_G3") (pintype "bidirectional"))
      (node (ref "J4") (pin "G4") (pinfunction "GND_4_G4") (pintype "bidirectional"))
      (node (ref "J4") (pin "P6") (pinfunction "VSS_P6") (pintype "bidirectional"))
      (node (ref "MCP73831") (pin "2") (pinfunction "VSS_2") (pintype "power_in"))
      (node (ref "R1_PWRUSB") (pin "1") (pinfunction "1_1") (pintype "passive"))
      (node (ref "R2") (pin "1") (pinfunction "1_1") (pintype "passive"))
      (node (ref "R2-USB") (pin "2") (pinfunction "2_2") (pintype "passive"))
      (node (ref "R2-USB1") (pin "1") (pinfunction "1_1") (pintype "passive"))
      (node (ref "R2_BAT") (pin "1") (pinfunction "1_1") (pintype "passive"))
      (node (ref "R4") (pin "1") (pinfunction "1_1") (pintype "passive"))
      (node (ref "RESET_BUTTON") (pin "1") (pinfunction "1_1") (pintype "passive"))
      (node (ref "RESET_BUTTON") (pin "2") (pinfunction "2_2") (pintype "passive"))
      (node (ref "SENSOR2") (pin "1") (pinfunction "GND_1") (pintype "power_in"))
      (node (ref "SENSOR2") (pin "5") (pinfunction "SDO_5") (pintype "bidirectional"))
      (node (ref "SENSOR2") (pin "7") (pinfunction "GND_7") (pintype "power_in"))
      (node (ref "SJ1") (pin "1") (pinfunction "1_1") (pintype "passive"))
      (node (ref "TP4") (pin "TP") (pinfunction "TP_TP") (pintype "input"))
      (node (ref "TP5") (pin "TP") (pinfunction "TP_TP") (pintype "input"))
      (node (ref "U1") (pin "4") (pinfunction "GND_4") (pintype "power_in"))
      (node (ref "U1") (pin "9") (pinfunction "EXP_9") (pintype "passive"))
      (node (ref "U2") (pin "1") (pinfunction "GND_1") (pintype "power_in"))
      (node (ref "U2") (pin "28") (pinfunction "GND_28") (pintype "power_in"))
      (node (ref "U2") (pin "29_1") (pinfunction "GND_29_1") (pintype "power_in"))
      (node (ref "U2") (pin "29_2") (pinfunction "GND_29_2") (pintype "power_in"))
      (node (ref "U2") (pin "29_3") (pinfunction "GND_29_3") (pintype "power_in"))
      (node (ref "U2") (pin "29_4") (pinfunction "GND_29_4") (pintype "power_in"))
      (node (ref "U2") (pin "29_5") (pinfunction "GND_29_5") (pintype "power_in"))
      (node (ref "U2") (pin "29_6") (pinfunction "GND_29_6") (pintype "power_in"))
      (node (ref "U2") (pin "29_7") (pinfunction "GND_29_7") (pintype "power_in"))
      (node (ref "U2") (pin "29_8") (pinfunction "GND_29_8") (pintype "power_in"))
      (node (ref "U2") (pin "29_9") (pinfunction "GND_29_9") (pintype "power_in"))
      (node (ref "U3") (pin "13") (pinfunction "GND_13") (pintype "power_in"))
      (node (ref "U4") (pin "1") (pinfunction "CTG_1") (pintype "power_in"))
      (node (ref "U4") (pin "4") (pinfunction "GND_4") (pintype "power_in"))
      (node (ref "U4") (pin "6") (pinfunction "QSTRT_6") (pintype "input"))
      (node (ref "U4") (pin "9") (pinfunction "EP_9") (pintype "power_in"))
    )
    (net (code "14") (name "GPIO8") (class "Default")
      (node (ref "R1") (pin "2") (pinfunction "2_2") (pintype "passive"))
      (node (ref "U2") (pin "10") (pinfunction "IO8_10") (pintype "bidirectional"))
    )
    (net (code "15") (name "I2C_PW") (class "Default")
      (node (ref "C1") (pin "1") (pinfunction "1_1") (pintype "passive"))
      (node (ref "C2") (pin "1") (pinfunction "1_1") (pintype "passive"))
      (node (ref "R1_PINH") (pin "1") (pinfunction "1_1") (pintype "passive"))
      (node (ref "R2-PINH") (pin "1") (pinfunction "1_1") (pintype "passive"))
      (node (ref "SENSOR2") (pin "2") (pinfunction "CSB_2") (pintype "input"))
      (node (ref "SENSOR2") (pin "6") (pinfunction "VDDIO_6") (pintype "power_in"))
      (node (ref "SENSOR2") (pin "8") (pinfunction "VDD_8") (pintype "power_in"))
      (node (ref "U2") (pin "17") (pinfunction "IO19_17") (pintype "bidirectional"))
    )
    (net (code "16") (name "INT_RTC") (class "Default")
      (node (ref "R1_PINH1") (pin "1") (pinfunction "1_1") (pintype "passive"))
      (node (ref "TP15") (pin "TP") (pinfunction "TP_TP") (pintype "input"))
      (node (ref "U2") (pin "8") (pinfunction "IO0_8") (pintype "bidirectional"))
      (node (ref "U3") (pin "3") (pinfunction "SQW/~{INT}_3") (pintype "output"))
    )
    (net (code "17") (name "IO{slash}BOOT") (class "Default")
      (node (ref "BOOT_BUTTON") (pin "3") (pinfunction "3_3") (pintype "passive"))
      (node (ref "BOOT_BUTTON") (pin "4") (pinfunction "4_4") (pintype "passive"))
      (node (ref "C6") (pin "1") (pinfunction "1_1") (pintype "passive"))
      (node (ref "R_BOOT") (pin "2") (pinfunction "2_2") (pintype "passive"))
      (node (ref "U2") (pin "15") (pinfunction "IO9_15") (pintype "bidirectional"))
    )
    (net (code "18") (name "IO{slash}CHANGE") (class "Default")
      (node (ref "C10") (pin "1") (pinfunction "1_1") (pintype "passive"))
      (node (ref "CHANGE_BUTTON") (pin "3") (pinfunction "3_3") (pintype "passive"))
      (node (ref "CHANGE_BUTTON") (pin "4") (pinfunction "4_4") (pintype "passive"))
      (node (ref "R_CHANGE") (pin "2") (pinfunction "2_2") (pintype "passive"))
      (node (ref "U2") (pin "23") (pinfunction "IO15_23") (pintype "bidirectional"))
    )
    (net (code "19") (name "MISO") (class "Default")
      (node (ref "D12") (pin "2") (pinfunction "2_2") (pintype "passive"))
      (node (ref "J4") (pin "P7") (pinfunction "DAT0_P7") (pintype "bidirectional"))
      (node (ref "R8") (pin "1") (pinfunction "1_1") (pintype "passive"))
      (node (ref "TP6") (pin "TP") (pinfunction "TP_TP") (pintype "input"))
      (node (ref "U1") (pin "2") (pinfunction "DO(IO1)_2") (pintype "bidirectional"))
      (node (ref "U2") (pin "27") (pinfunction "IO2_27") (pintype "bidirectional"))
    )
    (net (code "20") (name "MOSI") (class "Default")
      (node (ref "D11") (pin "2") (pinfunction "2_2") (pintype "passive"))
      (node (ref "J1") (pin "14") (pinfunction "14_14") (pintype "bidirectional"))
      (node (ref "J4") (pin "P3") (pinfunction "CMD_P3") (pintype "bidirectional"))
      (node (ref "R7") (pin "1") (pinfunction "1_1") (pintype "passive"))
      (node (ref "TP7") (pin "TP") (pinfunction "TP_TP") (pintype "input"))
      (node (ref "U1") (pin "5") (pinfunction "DI(IO0)_5") (pintype "bidirectional"))
      (node (ref "U2") (pin "7") (pinfunction "IO7_7") (pintype "bidirectional"))
    )
    (net (code "21") (name "Net-(CHG_LED-PadC)") (class "Default")
      (node (ref "CHG_LED") (pin "C") (pinfunction "C_C") (pintype "passive"))
      (node (ref "R1_BAT") (pin "1") (pinfunction "1_1") (pintype "passive"))
    )
    (net (code "22") (name "Net-(D2-CATHODE)") (class "Default")
      (node (ref "C1_BAT1") (pin "1") (pinfunction "1_1") (pintype "passive"))
      (node (ref "D2") (pin "1") (pinfunction "CATHODE_1") (pintype "bidirectional"))
      (node (ref "Q1") (pin "2") (pinfunction "S_2") (pintype "bidirectional"))
    )
    (net (code "23") (name "Net-(D3-A)") (class "Default")
      (node (ref "C4") (pin "1") (pinfunction "1_1") (pintype "passive"))
      (node (ref "D3") (pin "2") (pinfunction "A_2") (pintype "bidirectional"))
      (node (ref "D4") (pin "1") (pinfunction "K_1") (pintype "bidirectional"))
    )
    (net (code "24") (name "Net-(D7-CATHODE)") (class "Default")
      (node (ref "D7") (pin "1") (pinfunction "CATHODE_1") (pintype "bidirectional"))
      (node (ref "R_CAPACITOR") (pin "1") (pinfunction "1_1") (pintype "passive"))
    )
    (net (code "25") (name "Net-(EPD_C1-Pad1)") (class "Default")
      (node (ref "EPD_C1") (pin "1") (pinfunction "1_1") (pintype "passive"))
      (node (ref "J1") (pin "5") (pinfunction "5_5") (pintype "bidirectional"))
    )
    (net (code "26") (name "Net-(EPD_C2-Pad1)") (class "Default")
      (node (ref "EPD_C2") (pin "1") (pinfunction "1_1") (pintype "passive"))
      (node (ref "J1") (pin "4") (pinfunction "4_4") (pintype "bidirectional"))
    )
    (net (code "27") (name "Net-(EPD_C6-Pad1)") (class "Default")
      (node (ref "EPD_C6") (pin "1") (pinfunction "1_1") (pintype "passive"))
      (node (ref "J1") (pin "18") (pinfunction "18_18") (pintype "bidirectional"))
    )
    (net (code "28") (name "Net-(EPD_C7-Pad1)") (class "Default")
      (node (ref "EPD_C7") (pin "1") (pinfunction "1_1") (pintype "passive"))
      (node (ref "J1") (pin "19") (pinfunction "19_19") (pintype "bidirectional"))
    )
    (net (code "29") (name "Net-(EPD_C8-Pad1)") (class "Default")
      (node (ref "EPD_C8") (pin "1") (pinfunction "1_1") (pintype "passive"))
      (node (ref "J1") (pin "20") (pinfunction "20_20") (pintype "bidirectional"))
    )
    (net (code "30") (name "Net-(EPD_C10-Pad1)") (class "Default")
      (node (ref "EPD_C10") (pin "1") (pinfunction "1_1") (pintype "passive"))
      (node (ref "J1") (pin "22") (pinfunction "22_22") (pintype "bidirectional"))
    )
    (net (code "31") (name "Net-(EPD_C12-Pad1)") (class "Default")
      (node (ref "EPD_C12") (pin "1") (pinfunction "1_1") (pintype "passive"))
      (node (ref "J1") (pin "24") (pinfunction "24_24") (pintype "bidirectional"))
    )
    (net (code "32") (name "Net-(IC1-CT)") (class "Default")
      (node (ref "C_DELAY") (pin "1") (pinfunction "1_1") (pintype "passive"))
      (node (ref "IC1") (pin "5") (pinfunction "CT_5") (pintype "bidirectional"))
    )
    (net (code "33") (name "Net-(J2-PadA5)") (class "Default")
      (node (ref "J2") (pin "A5") (pinfunction "A5_A5") (pintype "bidirectional"))
      (node (ref "R2-USB1") (pin "2") (pinfunction "2_2") (pintype "passive"))
    )
    (net (code "34") (name "Net-(J2-PadB5)") (class "Default")
      (node (ref "J2") (pin "B5") (pinfunction "B5_B5") (pintype "bidirectional"))
      (node (ref "R2-USB") (pin "1") (pinfunction "1_1") (pintype "passive"))
    )
    (net (code "35") (name "Net-(MCP73831-PROG)") (class "Default")
      (node (ref "MCP73831") (pin "5") (pinfunction "PROG_5") (pintype "input"))
      (node (ref "R2_BAT") (pin "2") (pinfunction "2_2") (pintype "passive"))
    )
    (net (code "36") (name "Net-(MCP73831-STAT)") (class "Default")
      (node (ref "MCP73831") (pin "1") (pinfunction "STAT_1") (pintype "output"))
      (node (ref "R1_BAT") (pin "2") (pinfunction "2_2") (pintype "passive"))
    )
    (net (code "37") (name "PREVGH") (class "Default")
      (node (ref "D5") (pin "1") (pinfunction "K_1") (pintype "bidirectional"))
      (node (ref "EPD_C9") (pin "1") (pinfunction "1_1") (pintype "passive"))
      (node (ref "J1") (pin "21") (pinfunction "21_21") (pintype "bidirectional"))
    )
    (net (code "38") (name "PREVGL") (class "Default")
      (node (ref "D4") (pin "2") (pinfunction "A_2") (pintype "bidirectional"))
      (node (ref "EPD_C11") (pin "1") (pinfunction "1_1") (pintype "passive"))
      (node (ref "J1") (pin "23") (pinfunction "23_23") (pintype "bidirectional"))
    )
    (net (code "39") (name "RESE") (class "Default")
      (node (ref "J1") (pin "3") (pinfunction "3_3") (pintype "bidirectional"))
      (node (ref "Q3") (pin "2") (pinfunction "S_2") (pintype "bidirectional"))
      (node (ref "R3") (pin "1") (pinfunction "1_1") (pintype "passive"))
    )
    (net (code "40") (name "RESE'") (class "Default")
      (node (ref "R2") (pin "2") (pinfunction "2_2") (pintype "passive"))
      (node (ref "R3") (pin "2") (pinfunction "2_2") (pintype "passive"))
      (node (ref "SJ1") (pin "2") (pinfunction "2_2") (pintype "passive"))
    )
    (net (code "41") (name "RESET") (class "Default")
      (node (ref "C5") (pin "1") (pinfunction "1_1") (pintype "passive"))
      (node (ref "IC1") (pin "1") (pinfunction "VOUT_1") (pintype "bidirectional"))
      (node (ref "RESET_BUTTON") (pin "3") (pinfunction "3_3") (pintype "passive"))
      (node (ref "RESET_BUTTON") (pin "4") (pinfunction "4_4") (pintype "passive"))
      (node (ref "R_RESET") (pin "2") (pinfunction "2_2") (pintype "passive"))
      (node (ref "U2") (pin "3") (pinfunction "EN_3") (pintype "input"))
    )
    (net (code "42") (name "RTC_RST") (class "Default")
      (node (ref "U2") (pin "16") (pinfunction "IO18_16") (pintype "bidirectional"))
      (node (ref "U3") (pin "4") (pinfunction "~{RST}_4") (pintype "input"))
    )
    (net (code "43") (name "RX") (class "Default")
      (node (ref "TP2") (pin "TP") (pinfunction "TP_TP") (pintype "input"))
      (node (ref "U2") (pin "24") (pinfunction "RXD0/GPIO17_24") (pintype "bidirectional"))
    )
    (net (code "44") (name "SCK") (class "Default")
      (node (ref "D10") (pin "2") (pinfunction "2_2") (pintype "passive"))
      (node (ref "J1") (pin "13") (pinfunction "13_13") (pintype "bidirectional"))
      (node (ref "J4") (pin "P5") (pinfunction "CLK_P5") (pintype "bidirectional"))
      (node (ref "R6") (pin "1") (pinfunction "1_1") (pintype "passive"))
      (node (ref "TP8") (pin "TP") (pinfunction "TP_TP") (pintype "input"))
      (node (ref "U1") (pin "6") (pinfunction "CLK_6") (pintype "input"))
      (node (ref "U2") (pin "6") (pinfunction "IO6_6") (pintype "bidirectional"))
    )
    (net (code "45") (name "SCL") (class "Default")
      (node (ref "J3") (pin "4") (pinfunction "4_4") (pintype "passive"))
      (node (ref "R2-PINH") (pin "2") (pinfunction "2_2") (pintype "passive"))
      (node (ref "SENSOR2") (pin "4") (pinfunction "SCK_4") (pintype "input"))
      (node (ref "U2") (pin "20") (pinfunction "IO22_20") (pintype "bidirectional"))
      (node (ref "U3") (pin "16") (pinfunction "SCL_16") (pintype "input"))
      (node (ref "U4") (pin "7") (pinfunction "SCL_7") (pintype "input"))
    )
    (net (code "46") (name "SDA") (class "Default")
      (node (ref "J3") (pin "3") (pinfunction "3_3") (pintype "passive"))
      (node (ref "R1_PINH") (pin "2") (pinfunction "2_2") (pintype "passive"))
      (node (ref "SENSOR2") (pin "3") (pinfunction "SDI_3") (pintype "bidirectional"))
      (node (ref "U2") (pin "19") (pinfunction "IO21_19") (pintype "bidirectional"))
      (node (ref "U3") (pin "15") (pinfunction "SDA_15") (pintype "bidirectional"))
      (node (ref "U4") (pin "8") (pinfunction "SDA_8") (pintype "bidirectional"))
    )
    (net (code "47") (name "SRC") (class "Default")
      (node (ref "C4") (pin "2") (pinfunction "2_2") (pintype "passive"))
      (node (ref "D5") (pin "2") (pinfunction "A_2") (pintype "bidirectional"))
      (node (ref "L1") (pin "1") (pinfunction "1_1") (pintype "passive"))
      (node (ref "Q3") (pin "3") (pinfunction "D_3") (pintype "bidirectional"))
    )
    (net (code "48") (name "SS_SD") (class "Default")
      (node (ref "D8") (pin "2") (pinfunction "2_2") (pintype "passive"))
      (node (ref "J4") (pin "P2") (pinfunction "CD/DAT3_P2") (pintype "bidirectional"))
      (node (ref "R10") (pin "1") (pinfunction "1_1") (pintype "passive"))
      (node (ref "U2") (pin "4") (pinfunction "IO4_4") (pintype "bidirectional"))
    )
    (net (code "49") (name "TX") (class "Default")
      (node (ref "TP1") (pin "TP") (pinfunction "TP_TP") (pintype "input"))
      (node (ref "U2") (pin "25") (pinfunction "TXD0/GPIO16_25") (pintype "bidirectional"))
    )
    (net (code "50") (name "USB_D") (class "Default")
      (node (ref "D1") (pin "3") (pinfunction "I/O2_1_3") (pintype "bidirectional"))
    )
    (net (code "51") (name "USB_D+") (class "Default")
      (node (ref "D1") (pin "1") (pinfunction "I/O1_1_1") (pintype "bidirectional"))
      (node (ref "U2") (pin "14") (pinfunction "IO13_14") (pintype "bidirectional"))
    )
    (net (code "52") (name "USB_D-") (class "Default")
      (node (ref "U2") (pin "13") (pinfunction "IO12_13") (pintype "bidirectional"))
    )
    (net (code "53") (name "VBAT") (class "Default")
      (node (ref "C2_BAT") (pin "2") (pinfunction "2_2") (pintype "passive"))
      (node (ref "MCP73831") (pin "3") (pinfunction "VBAT_3") (pintype "power_in"))
      (node (ref "Q1") (pin "3") (pinfunction "D_3") (pintype "bidirectional"))
      (node (ref "TP3") (pin "TP") (pinfunction "TP_TP") (pintype "input"))
      (node (ref "U4") (pin "2") (pinfunction "CELL_2") (pintype "power_in"))
      (node (ref "U4") (pin "3") (pinfunction "VDD_3") (pintype "power_in"))
    )
    (net (code "54") (name "VBUS") (class "Default")
      (node (ref "C1_BAT") (pin "2") (pinfunction "2_2") (pintype "passive"))
      (node (ref "C4_USB") (pin "1") (pinfunction "1_1") (pintype "passive"))
      (node (ref "C5_USB") (pin "1") (pinfunction "1_1") (pintype "passive"))
      (node (ref "CHG_LED") (pin "A") (pinfunction "A_A") (pintype "passive"))
      (node (ref "D1") (pin "5") (pinfunction "VBUS_5") (pintype "bidirectional"))
      (node (ref "D2") (pin "2") (pinfunction "ANODE_2") (pintype "bidirectional"))
      (node (ref "J2") (pin "B9") (pinfunction "B9_B9") (pintype "bidirectional"))
      (node (ref "MCP73831") (pin "4") (pinfunction "VIN_4") (pintype "power_in"))
      (node (ref "PFMF.050.1") (pin "2") (pinfunction "2_2") (pintype "passive"))
      (node (ref "Q1") (pin "1") (pinfunction "G_1") (pintype "bidirectional"))
      (node (ref "R1_PWRUSB") (pin "2") (pinfunction "2_2") (pintype "passive"))
      (node (ref "TP14") (pin "TP") (pinfunction "TP_TP") (pintype "input"))
    )
    (net (code "55") (name "VRTC") (class "Default")
      (node (ref "C10_SUPERCAP") (pin "2") (pinfunction "2_2") (pintype "passive"))
      (node (ref "C8") (pin "1") (pinfunction "1_1") (pintype "passive"))
      (node (ref "R_CAPACITOR") (pin "2") (pinfunction "2_2") (pintype "passive"))
      (node (ref "U3") (pin "14") (pinfunction "VBAT_14") (pintype "power_in"))
    )
    (net (code "56") (name "VUSB") (class "Default")
      (node (ref "J2") (pin "A4") (pinfunction "A4_A4") (pintype "bidirectional"))
      (node (ref "J2") (pin "A9") (pinfunction "A9_A9") (pintype "bidirectional"))
      (node (ref "J2") (pin "B4") (pinfunction "B4_B4") (pintype "bidirectional"))
      (node (ref "PFMF.050.1") (pin "1") (pinfunction "1_1") (pintype "passive"))
    )
    (net (code "57") (name "unconnected-(IC1-NC-Pad4)") (class "Default")
      (node (ref "IC1") (pin "4") (pinfunction "NC_4") (pintype "no_connect"))
    )
    (net (code "58") (name "unconnected-(IC4-NC-Pad4)") (class "Default")
      (node (ref "IC4") (pin "4") (pinfunction "NC_4") (pintype "no_connect"))
    )
    (net (code "59") (name "unconnected-(J1-Pad1)") (class "Default")
      (node (ref "J1") (pin "1") (pinfunction "1_1") (pintype "bidirectional"))
    )
    (net (code "60") (name "unconnected-(J1-Pad6)") (class "Default")
      (node (ref "J1") (pin "6") (pinfunction "6_6") (pintype "bidirectional"))
    )
    (net (code "61") (name "unconnected-(J1-Pad7)") (class "Default")
      (node (ref "J1") (pin "7") (pinfunction "7_7") (pintype "bidirectional"))
    )
    (net (code "62") (name "unconnected-(J2-PadA8)") (class "Default")
      (node (ref "J2") (pin "A8") (pinfunction "A8_A8") (pintype "bidirectional"))
    )
    (net (code "63") (name "unconnected-(J2-PadB8)") (class "Default")
      (node (ref "J2") (pin "B8") (pinfunction "B8_B8") (pintype "bidirectional"))
    )
    (net (code "64") (name "unconnected-(J4-DAT1-PadP8)") (class "Default")
      (node (ref "J4") (pin "P8") (pinfunction "DAT1_P8") (pintype "bidirectional"))
    )
    (net (code "65") (name "unconnected-(J4-DAT2-PadP1)") (class "Default")
      (node (ref "J4") (pin "P1") (pinfunction "DAT2_P1") (pintype "bidirectional"))
    )
    (net (code "66") (name "unconnected-(J4-DETECTION_1-PadS1)") (class "Default")
      (node (ref "J4") (pin "S1") (pinfunction "DETECTION_1_S1") (pintype "bidirectional"))
    )
    (net (code "67") (name "unconnected-(J4-DETECTION_2-PadS2)") (class "Default")
      (node (ref "J4") (pin "S2") (pinfunction "DETECTION_2_S2") (pintype "bidirectional"))
    )
    (net (code "68") (name "unconnected-(U2-NC-Pad22)") (class "Default")
      (node (ref "U2") (pin "22") (pinfunction "NC_22") (pintype "no_connect"))
    )
    (net (code "69") (name "unconnected-(U4-~{ALERT}-Pad5)") (class "Default")
      (node (ref "U4") (pin "5") (pinfunction "~{ALERT}_5") (pintype "output"))
    )
  )
)
